# Hercules.net
KiCad netlist of a schematic drawn in EAGLE
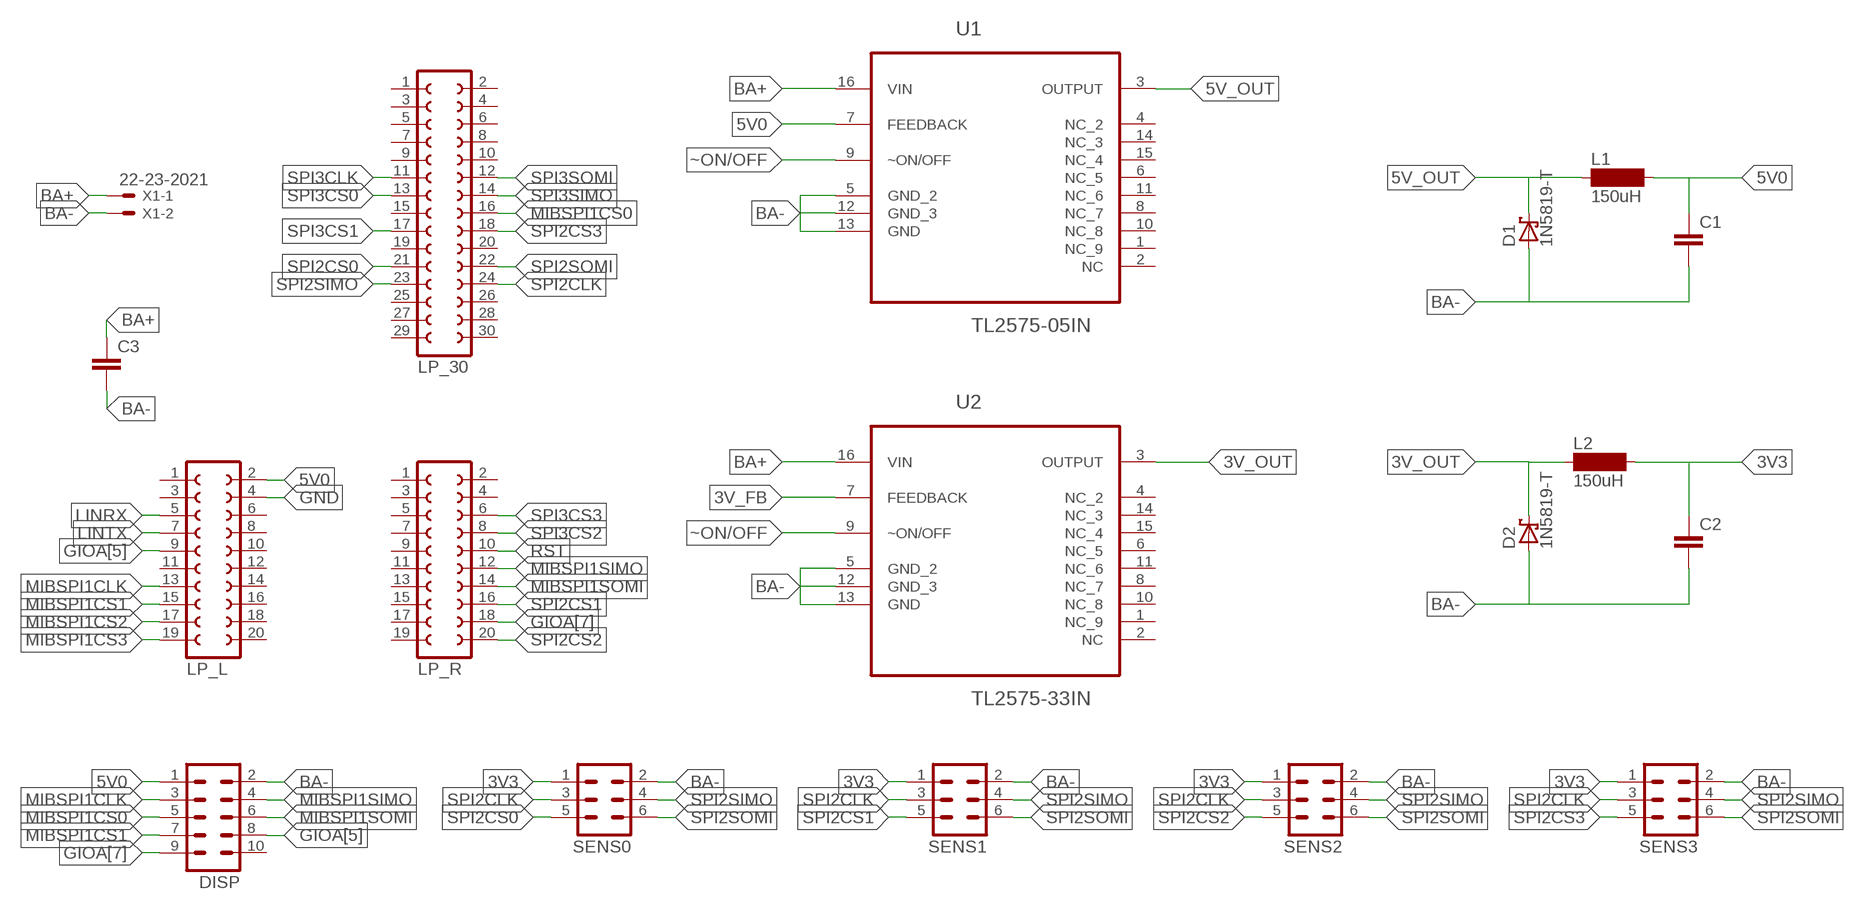
[diagram p0: schematic, sheet 1]

(export (version "E")
  (design (tool "Eeschema 10.0.6"))
  (components
    (comp (ref "C1")
      (value "C7.5/6")
      (footprint "eagle-import:C7.5B6")
      (libsource (lib "eagle-import") (part "C7.5/6"))
    )
    (comp (ref "C2")
      (value "C7.5/6")
      (footprint "eagle-import:C7.5B6")
      (libsource (lib "eagle-import") (part "C7.5/6"))
    )
    (comp (ref "C3")
      (value "C2.5/5")
      (footprint "eagle-import:C2.5-5")
      (libsource (lib "eagle-import") (part "C2.5/5"))
    )
    (comp (ref "D1")
      (value "1N5819-T")
      (footprint "eagle-import:DO41-7.6")
      (libsource (lib "eagle-import") (part "1N5819-T"))
    )
    (comp (ref "D2")
      (value "1N5819-T")
      (footprint "eagle-import:DO41-7.6")
      (libsource (lib "eagle-import") (part "1N5819-T"))
    )
    (comp (ref "DISP")
      (value "MA05-2")
      (footprint "eagle-import:MA05-2")
      (libsource (lib "eagle-import") (part "MA05-2"))
    )
    (comp (ref "L1")
      (value "150uH")
      (footprint "eagle-import:BS75")
      (libsource (lib "eagle-import") (part "BS75"))
    )
    (comp (ref "L2")
      (value "150uH")
      (footprint "eagle-import:BS75")
      (libsource (lib "eagle-import") (part "BS75"))
    )
    (comp (ref "LP_30")
      (value "FE15-2")
      (footprint "eagle-import:FE15-2")
      (libsource (lib "eagle-import") (part "FE15-2"))
    )
    (comp (ref "LP_L")
      (value "FE10-2")
      (footprint "eagle-import:FE10-2")
      (libsource (lib "eagle-import") (part "FE10-2"))
    )
    (comp (ref "LP_R")
      (value "FE10-2")
      (footprint "eagle-import:FE10-2")
      (libsource (lib "eagle-import") (part "FE10-2"))
    )
    (comp (ref "SENS0")
      (value "MA03-2")
      (footprint "eagle-import:MA03-2")
      (libsource (lib "eagle-import") (part "MA03-2"))
    )
    (comp (ref "SENS1")
      (value "MA03-2")
      (footprint "eagle-import:MA03-2")
      (libsource (lib "eagle-import") (part "MA03-2"))
    )
    (comp (ref "SENS2")
      (value "MA03-2")
      (footprint "eagle-import:MA03-2")
      (libsource (lib "eagle-import") (part "MA03-2"))
    )
    (comp (ref "SENS3")
      (value "MA03-2")
      (footprint "eagle-import:MA03-2")
      (libsource (lib "eagle-import") (part "MA03-2"))
    )
    (comp (ref "U1")
      (value "TL2575-05IN")
      (footprint "eagle-import:DIP254P762X508-16")
      (fields (field (name "MPN") "TL2575HV-05IN"))
      (libsource (lib "eagle-import") (part "TL2575-05IN"))
    )
    (comp (ref "U2")
      (value "TL2575-33IN")
      (footprint "eagle-import:DIP254P762X508-16")
      (fields (field (name "MPN") "TL2575HV-05IN"))
      (libsource (lib "eagle-import") (part "TL2575-33IN"))
    )
    (comp (ref "X1")
      (value "22-23-2021")
      (footprint "eagle-import:22-23-2021")
      (fields (field (name "MF") "MOLEX"))
      (libsource (lib "eagle-import") (part "22-23-2021"))
    )
  )
  (nets
    (net (code "1") (name "/~{ON{slash}OFF}") (class "Default")
      (node (ref "U1") (pin "9") (pinfunction "~{ON/OFF}_9") (pintype "input"))
      (node (ref "U2") (pin "9") (pinfunction "~{ON/OFF}_9") (pintype "input"))
    )
    (net (code "2") (name "3V3") (class "Default")
      (node (ref "C2") (pin "1") (pinfunction "1_1") (pintype "passive"))
      (node (ref "L2") (pin "2") (pinfunction "2_2") (pintype "passive"))
      (node (ref "SENS0") (pin "1") (pinfunction "1_1") (pintype "passive"))
      (node (ref "SENS1") (pin "1") (pinfunction "1_1") (pintype "passive"))
      (node (ref "SENS2") (pin "1") (pinfunction "1_1") (pintype "passive"))
      (node (ref "SENS3") (pin "1") (pinfunction "1_1") (pintype "passive"))
    )
    (net (code "3") (name "3V_FB") (class "Default")
      (node (ref "U2") (pin "7") (pinfunction "FEEDBACK_7") (pintype "bidirectional"))
    )
    (net (code "4") (name "3V_OUT") (class "Default")
      (node (ref "D2") (pin "C") (pinfunction "C_C") (pintype "passive"))
      (node (ref "L2") (pin "1") (pinfunction "1_1") (pintype "passive"))
      (node (ref "U2") (pin "3") (pinfunction "OUTPUT_3") (pintype "output"))
    )
    (net (code "5") (name "5V0") (class "Default")
      (node (ref "C1") (pin "1") (pinfunction "1_1") (pintype "passive"))
      (node (ref "DISP") (pin "1") (pinfunction "1_1") (pintype "passive"))
      (node (ref "L1") (pin "2") (pinfunction "2_2") (pintype "passive"))
      (node (ref "LP_L") (pin "2") (pinfunction "2_2") (pintype "passive"))
      (node (ref "U1") (pin "7") (pinfunction "FEEDBACK_7") (pintype "bidirectional"))
    )
    (net (code "6") (name "5V_OUT") (class "Default")
      (node (ref "D1") (pin "C") (pinfunction "C_C") (pintype "passive"))
      (node (ref "L1") (pin "1") (pinfunction "1_1") (pintype "passive"))
      (node (ref "U1") (pin "3") (pinfunction "OUTPUT_3") (pintype "output"))
    )
    (net (code "7") (name "BA+") (class "Default")
      (node (ref "C3") (pin "1") (pinfunction "1_1") (pintype "passive"))
      (node (ref "U1") (pin "16") (pinfunction "VIN_16") (pintype "power_in"))
      (node (ref "U2") (pin "16") (pinfunction "VIN_16") (pintype "power_in"))
      (node (ref "X1") (pin "1") (pinfunction "S_1") (pintype "passive"))
    )
    (net (code "8") (name "BA-") (class "Default")
      (node (ref "C1") (pin "2") (pinfunction "2_2") (pintype "passive"))
      (node (ref "C2") (pin "2") (pinfunction "2_2") (pintype "passive"))
      (node (ref "C3") (pin "2") (pinfunction "2_2") (pintype "passive"))
      (node (ref "D1") (pin "A") (pinfunction "A_A") (pintype "passive"))
      (node (ref "D2") (pin "A") (pinfunction "A_A") (pintype "passive"))
      (node (ref "DISP") (pin "2") (pinfunction "2_2") (pintype "passive"))
      (node (ref "SENS0") (pin "2") (pinfunction "2_2") (pintype "passive"))
      (node (ref "SENS1") (pin "2") (pinfunction "2_2") (pintype "passive"))
      (node (ref "SENS2") (pin "2") (pinfunction "2_2") (pintype "passive"))
      (node (ref "SENS3") (pin "2") (pinfunction "2_2") (pintype "passive"))
      (node (ref "U1") (pin "12") (pinfunction "GND_3_12") (pintype "passive"))
      (node (ref "U1") (pin "13") (pinfunction "GND_13") (pintype "passive"))
      (node (ref "U1") (pin "5") (pinfunction "GND_2_5") (pintype "passive"))
      (node (ref "U2") (pin "12") (pinfunction "GND_3_12") (pintype "passive"))
      (node (ref "U2") (pin "13") (pinfunction "GND_13") (pintype "passive"))
      (node (ref "U2") (pin "5") (pinfunction "GND_2_5") (pintype "passive"))
      (node (ref "X1") (pin "2") (pinfunction "S_2") (pintype "passive"))
    )
    (net (code "9") (name "GIOA[5]") (class "Default")
      (node (ref "DISP") (pin "8") (pinfunction "8_8") (pintype "passive"))
      (node (ref "LP_L") (pin "9") (pinfunction "9_9") (pintype "passive"))
    )
    (net (code "10") (name "GIOA[7]") (class "Default")
      (node (ref "DISP") (pin "9") (pinfunction "9_9") (pintype "passive"))
      (node (ref "LP_R") (pin "18") (pinfunction "18_18") (pintype "passive"))
    )
    (net (code "11") (name "GND") (class "Default")
      (node (ref "LP_L") (pin "4") (pinfunction "4_4") (pintype "passive"))
    )
    (net (code "12") (name "LINRX") (class "Default")
      (node (ref "LP_L") (pin "5") (pinfunction "5_5") (pintype "passive"))
    )
    (net (code "13") (name "LINTX") (class "Default")
      (node (ref "LP_L") (pin "7") (pinfunction "7_7") (pintype "passive"))
    )
    (net (code "14") (name "MIBSPI1CLK") (class "Default")
      (node (ref "DISP") (pin "3") (pinfunction "3_3") (pintype "passive"))
      (node (ref "LP_L") (pin "13") (pinfunction "13_13") (pintype "passive"))
    )
    (net (code "15") (name "MIBSPI1CS0") (class "Default")
      (node (ref "DISP") (pin "5") (pinfunction "5_5") (pintype "passive"))
      (node (ref "LP_30") (pin "16") (pinfunction "16_16") (pintype "passive"))
    )
    (net (code "16") (name "MIBSPI1CS1") (class "Default")
      (node (ref "DISP") (pin "7") (pinfunction "7_7") (pintype "passive"))
      (node (ref "LP_L") (pin "15") (pinfunction "15_15") (pintype "passive"))
    )
    (net (code "17") (name "MIBSPI1CS2") (class "Default")
      (node (ref "LP_L") (pin "17") (pinfunction "17_17") (pintype "passive"))
    )
    (net (code "18") (name "MIBSPI1CS3") (class "Default")
      (node (ref "LP_L") (pin "19") (pinfunction "19_19") (pintype "passive"))
    )
    (net (code "19") (name "MIBSPI1SIMO") (class "Default")
      (node (ref "DISP") (pin "4") (pinfunction "4_4") (pintype "passive"))
      (node (ref "LP_R") (pin "12") (pinfunction "12_12") (pintype "passive"))
    )
    (net (code "20") (name "MIBSPI1SOMI") (class "Default")
      (node (ref "DISP") (pin "6") (pinfunction "6_6") (pintype "passive"))
      (node (ref "LP_R") (pin "14") (pinfunction "14_14") (pintype "passive"))
    )
    (net (code "21") (name "RST") (class "Default")
      (node (ref "LP_R") (pin "10") (pinfunction "10_10") (pintype "passive"))
    )
    (net (code "22") (name "SPI2CLK") (class "Default")
      (node (ref "LP_30") (pin "24") (pinfunction "24_24") (pintype "passive"))
      (node (ref "SENS0") (pin "3") (pinfunction "3_3") (pintype "passive"))
      (node (ref "SENS1") (pin "3") (pinfunction "3_3") (pintype "passive"))
      (node (ref "SENS2") (pin "3") (pinfunction "3_3") (pintype "passive"))
      (node (ref "SENS3") (pin "3") (pinfunction "3_3") (pintype "passive"))
    )
    (net (code "23") (name "SPI2CS0") (class "Default")
      (node (ref "LP_30") (pin "21") (pinfunction "21_21") (pintype "passive"))
      (node (ref "SENS0") (pin "5") (pinfunction "5_5") (pintype "passive"))
    )
    (net (code "24") (name "SPI2CS1") (class "Default")
      (node (ref "LP_R") (pin "16") (pinfunction "16_16") (pintype "passive"))
      (node (ref "SENS1") (pin "5") (pinfunction "5_5") (pintype "passive"))
    )
    (net (code "25") (name "SPI2CS2") (class "Default")
      (node (ref "LP_R") (pin "20") (pinfunction "20_20") (pintype "passive"))
      (node (ref "SENS2") (pin "5") (pinfunction "5_5") (pintype "passive"))
    )
    (net (code "26") (name "SPI2CS3") (class "Default")
      (node (ref "LP_30") (pin "18") (pinfunction "18_18") (pintype "passive"))
      (node (ref "SENS3") (pin "5") (pinfunction "5_5") (pintype "passive"))
    )
    (net (code "27") (name "SPI2SIMO") (class "Default")
      (node (ref "LP_30") (pin "23") (pinfunction "23_23") (pintype "passive"))
      (node (ref "SENS0") (pin "4") (pinfunction "4_4") (pintype "passive"))
      (node (ref "SENS1") (pin "4") (pinfunction "4_4") (pintype "passive"))
      (node (ref "SENS2") (pin "4") (pinfunction "4_4") (pintype "passive"))
      (node (ref "SENS3") (pin "4") (pinfunction "4_4") (pintype "passive"))
    )
    (net (code "28") (name "SPI2SOMI") (class "Default")
      (node (ref "LP_30") (pin "22") (pinfunction "22_22") (pintype "passive"))
      (node (ref "SENS0") (pin "6") (pinfunction "6_6") (pintype "passive"))
      (node (ref "SENS1") (pin "6") (pinfunction "6_6") (pintype "passive"))
      (node (ref "SENS2") (pin "6") (pinfunction "6_6") (pintype "passive"))
      (node (ref "SENS3") (pin "6") (pinfunction "6_6") (pintype "passive"))
    )
    (net (code "29") (name "SPI3CLK") (class "Default")
      (node (ref "LP_30") (pin "11") (pinfunction "11_11") (pintype "passive"))
    )
    (net (code "30") (name "SPI3CS0") (class "Default")
      (node (ref "LP_30") (pin "13") (pinfunction "13_13") (pintype "passive"))
    )
    (net (code "31") (name "SPI3CS1") (class "Default")
      (node (ref "LP_30") (pin "17") (pinfunction "17_17") (pintype "passive"))
    )
    (net (code "32") (name "SPI3CS2") (class "Default")
      (node (ref "LP_R") (pin "8") (pinfunction "8_8") (pintype "passive"))
    )
    (net (code "33") (name "SPI3CS3") (class "Default")
      (node (ref "LP_R") (pin "6") (pinfunction "6_6") (pintype "passive"))
    )
    (net (code "34") (name "SPI3SIMO") (class "Default")
      (node (ref "LP_30") (pin "14") (pinfunction "14_14") (pintype "passive"))
    )
    (net (code "35") (name "SPI3SOMI") (class "Default")
      (node (ref "LP_30") (pin "12") (pinfunction "12_12") (pintype "passive"))
    )
    (net (code "36") (name "unconnected-(DISP-Pad10)") (class "Default")
      (node (ref "DISP") (pin "10") (pinfunction "10_10") (pintype "passive"))
    )
    (net (code "37") (name "unconnected-(LP_30-Pad1)") (class "Default")
      (node (ref "LP_30") (pin "1") (pinfunction "1_1") (pintype "passive"))
    )
    (net (code "38") (name "unconnected-(LP_30-Pad2)") (class "Default")
      (node (ref "LP_30") (pin "2") (pinfunction "2_2") (pintype "passive"))
    )
    (net (code "39") (name "unconnected-(LP_30-Pad3)") (class "Default")
      (node (ref "LP_30") (pin "3") (pinfunction "3_3") (pintype "passive"))
    )
    (net (code "40") (name "unconnected-(LP_30-Pad4)") (class "Default")
      (node (ref "LP_30") (pin "4") (pinfunction "4_4") (pintype "passive"))
    )
    (net (code "41") (name "unconnected-(LP_30-Pad5)") (class "Default")
      (node (ref "LP_30") (pin "5") (pinfunction "5_5") (pintype "passive"))
    )
    (net (code "42") (name "unconnected-(LP_30-Pad6)") (class "Default")
      (node (ref "LP_30") (pin "6") (pinfunction "6_6") (pintype "passive"))
    )
    (net (code "43") (name "unconnected-(LP_30-Pad7)") (class "Default")
      (node (ref "LP_30") (pin "7") (pinfunction "7_7") (pintype "passive"))
    )
    (net (code "44") (name "unconnected-(LP_30-Pad8)") (class "Default")
      (node (ref "LP_30") (pin "8") (pinfunction "8_8") (pintype "passive"))
    )
    (net (code "45") (name "unconnected-(LP_30-Pad9)") (class "Default")
      (node (ref "LP_30") (pin "9") (pinfunction "9_9") (pintype "passive"))
    )
    (net (code "46") (name "unconnected-(LP_30-Pad10)") (class "Default")
      (node (ref "LP_30") (pin "10") (pinfunction "10_10") (pintype "passive"))
    )
    (net (code "47") (name "unconnected-(LP_30-Pad15)") (class "Default")
      (node (ref "LP_30") (pin "15") (pinfunction "15_15") (pintype "passive"))
    )
    (net (code "48") (name "unconnected-(LP_30-Pad19)") (class "Default")
      (node (ref "LP_30") (pin "19") (pinfunction "19_19") (pintype "passive"))
    )
    (net (code "49") (name "unconnected-(LP_30-Pad20)") (class "Default")
      (node (ref "LP_30") (pin "20") (pinfunction "20_20") (pintype "passive"))
    )
    (net (code "50") (name "unconnected-(LP_30-Pad25)") (class "Default")
      (node (ref "LP_30") (pin "25") (pinfunction "25_25") (pintype "passive"))
    )
    (net (code "51") (name "unconnected-(LP_30-Pad26)") (class "Default")
      (node (ref "LP_30") (pin "26") (pinfunction "26_26") (pintype "passive"))
    )
    (net (code "52") (name "unconnected-(LP_30-Pad27)") (class "Default")
      (node (ref "LP_30") (pin "27") (pinfunction "27_27") (pintype "passive"))
    )
    (net (code "53") (name "unconnected-(LP_30-Pad28)") (class "Default")
      (node (ref "LP_30") (pin "28") (pinfunction "28_28") (pintype "passive"))
    )
    (net (code "54") (name "unconnected-(LP_30-Pad29)") (class "Default")
      (node (ref "LP_30") (pin "29") (pinfunction "29_29") (pintype "passive"))
    )
    (net (code "55") (name "unconnected-(LP_30-Pad30)") (class "Default")
      (node (ref "LP_30") (pin "30") (pinfunction "30_30") (pintype "passive"))
    )
    (net (code "56") (name "unconnected-(LP_L-Pad1)") (class "Default")
      (node (ref "LP_L") (pin "1") (pinfunction "1_1") (pintype "passive"))
    )
    (net (code "57") (name "unconnected-(LP_L-Pad3)") (class "Default")
      (node (ref "LP_L") (pin "3") (pinfunction "3_3") (pintype "passive"))
    )
    (net (code "58") (name "unconnected-(LP_L-Pad6)") (class "Default")
      (node (ref "LP_L") (pin "6") (pinfunction "6_6") (pintype "passive"))
    )
    (net (code "59") (name "unconnected-(LP_L-Pad8)") (class "Default")
      (node (ref "LP_L") (pin "8") (pinfunction "8_8") (pintype "passive"))
    )
    (net (code "60") (name "unconnected-(LP_L-Pad10)") (class "Default")
      (node (ref "LP_L") (pin "10") (pinfunction "10_10") (pintype "passive"))
    )
    (net (code "61") (name "unconnected-(LP_L-Pad11)") (class "Default")
      (node (ref "LP_L") (pin "11") (pinfunction "11_11") (pintype "passive"))
    )
    (net (code "62") (name "unconnected-(LP_L-Pad12)") (class "Default")
      (node (ref "LP_L") (pin "12") (pinfunction "12_12") (pintype "passive"))
    )
    (net (code "63") (name "unconnected-(LP_L-Pad14)") (class "Default")
      (node (ref "LP_L") (pin "14") (pinfunction "14_14") (pintype "passive"))
    )
    (net (code "64") (name "unconnected-(LP_L-Pad16)") (class "Default")
      (node (ref "LP_L") (pin "16") (pinfunction "16_16") (pintype "passive"))
    )
    (net (code "65") (name "unconnected-(LP_L-Pad18)") (class "Default")
      (node (ref "LP_L") (pin "18") (pinfunction "18_18") (pintype "passive"))
    )
    (net (code "66") (name "unconnected-(LP_L-Pad20)") (class "Default")
      (node (ref "LP_L") (pin "20") (pinfunction "20_20") (pintype "passive"))
    )
    (net (code "67") (name "unconnected-(LP_R-Pad1)") (class "Default")
      (node (ref "LP_R") (pin "1") (pinfunction "1_1") (pintype "passive"))
    )
    (net (code "68") (name "unconnected-(LP_R-Pad2)") (class "Default")
      (node (ref "LP_R") (pin "2") (pinfunction "2_2") (pintype "passive"))
    )
    (net (code "69") (name "unconnected-(LP_R-Pad3)") (class "Default")
      (node (ref "LP_R") (pin "3") (pinfunction "3_3") (pintype "passive"))
    )
    (net (code "70") (name "unconnected-(LP_R-Pad4)") (class "Default")
      (node (ref "LP_R") (pin "4") (pinfunction "4_4") (pintype "passive"))
    )
    (net (code "71") (name "unconnected-(LP_R-Pad5)") (class "Default")
      (node (ref "LP_R") (pin "5") (pinfunction "5_5") (pintype "passive"))
    )
    (net (code "72") (name "unconnected-(LP_R-Pad7)") (class "Default")
      (node (ref "LP_R") (pin "7") (pinfunction "7_7") (pintype "passive"))
    )
    (net (code "73") (name "unconnected-(LP_R-Pad9)") (class "Default")
      (node (ref "LP_R") (pin "9") (pinfunction "9_9") (pintype "passive"))
    )
    (net (code "74") (name "unconnected-(LP_R-Pad11)") (class "Default")
      (node (ref "LP_R") (pin "11") (pinfunction "11_11") (pintype "passive"))
    )
    (net (code "75") (name "unconnected-(LP_R-Pad13)") (class "Default")
      (node (ref "LP_R") (pin "13") (pinfunction "13_13") (pintype "passive"))
    )
    (net (code "76") (name "unconnected-(LP_R-Pad15)") (class "Default")
      (node (ref "LP_R") (pin "15") (pinfunction "15_15") (pintype "passive"))
    )
    (net (code "77") (name "unconnected-(LP_R-Pad17)") (class "Default")
      (node (ref "LP_R") (pin "17") (pinfunction "17_17") (pintype "passive"))
    )
    (net (code "78") (name "unconnected-(LP_R-Pad19)") (class "Default")
      (node (ref "LP_R") (pin "19") (pinfunction "19_19") (pintype "passive"))
    )
    (net (code "79") (name "unconnected-(U1-NC-Pad2)") (class "Default")
      (node (ref "U1") (pin "2") (pinfunction "NC_2") (pintype "no_connect"))
    )
    (net (code "80") (name "unconnected-(U1-NC_2-Pad4)") (class "Default")
      (node (ref "U1") (pin "4") (pinfunction "NC_2_4") (pintype "no_connect"))
    )
    (net (code "81") (name "unconnected-(U1-NC_3-Pad14)") (class "Default")
      (node (ref "U1") (pin "14") (pinfunction "NC_3_14") (pintype "no_connect"))
    )
    (net (code "82") (name "unconnected-(U1-NC_4-Pad15)") (class "Default")
      (node (ref "U1") (pin "15") (pinfunction "NC_4_15") (pintype "no_connect"))
    )
    (net (code "83") (name "unconnected-(U1-NC_5-Pad6)") (class "Default")
      (node (ref "U1") (pin "6") (pinfunction "NC_5_6") (pintype "no_connect"))
    )
    (net (code "84") (name "unconnected-(U1-NC_6-Pad11)") (class "Default")
      (node (ref "U1") (pin "11") (pinfunction "NC_6_11") (pintype "no_connect"))
    )
    (net (code "85") (name "unconnected-(U1-NC_7-Pad8)") (class "Default")
      (node (ref "U1") (pin "8") (pinfunction "NC_7_8") (pintype "no_connect"))
    )
    (net (code "86") (name "unconnected-(U1-NC_8-Pad10)") (class "Default")
      (node (ref "U1") (pin "10") (pinfunction "NC_8_10") (pintype "no_connect"))
    )
    (net (code "87") (name "unconnected-(U1-NC_9-Pad1)") (class "Default")
      (node (ref "U1") (pin "1") (pinfunction "NC_9_1") (pintype "no_connect"))
    )
    (net (code "88") (name "unconnected-(U2-NC-Pad2)") (class "Default")
      (node (ref "U2") (pin "2") (pinfunction "NC_2") (pintype "no_connect"))
    )
    (net (code "89") (name "unconnected-(U2-NC_2-Pad4)") (class "Default")
      (node (ref "U2") (pin "4") (pinfunction "NC_2_4") (pintype "no_connect"))
    )
    (net (code "90") (name "unconnected-(U2-NC_3-Pad14)") (class "Default")
      (node (ref "U2") (pin "14") (pinfunction "NC_3_14") (pintype "no_connect"))
    )
    (net (code "91") (name "unconnected-(U2-NC_4-Pad15)") (class "Default")
      (node (ref "U2") (pin "15") (pinfunction "NC_4_15") (pintype "no_connect"))
    )
    (net (code "92") (name "unconnected-(U2-NC_5-Pad6)") (class "Default")
      (node (ref "U2") (pin "6") (pinfunction "NC_5_6") (pintype "no_connect"))
    )
    (net (code "93") (name "unconnected-(U2-NC_6-Pad11)") (class "Default")
      (node (ref "U2") (pin "11") (pinfunction "NC_6_11") (pintype "no_connect"))
    )
    (net (code "94") (name "unconnected-(U2-NC_7-Pad8)") (class "Default")
      (node (ref "U2") (pin "8") (pinfunction "NC_7_8") (pintype "no_connect"))
    )
    (net (code "95") (name "unconnected-(U2-NC_8-Pad10)") (class "Default")
      (node (ref "U2") (pin "10") (pinfunction "NC_8_10") (pintype "no_connect"))
    )
    (net (code "96") (name "unconnected-(U2-NC_9-Pad1)") (class "Default")
      (node (ref "U2") (pin "1") (pinfunction "NC_9_1") (pintype "no_connect"))
    )
  )
)
